# TM_Programmer0_1.net
KiCad netlist of a schematic drawn in EAGLE
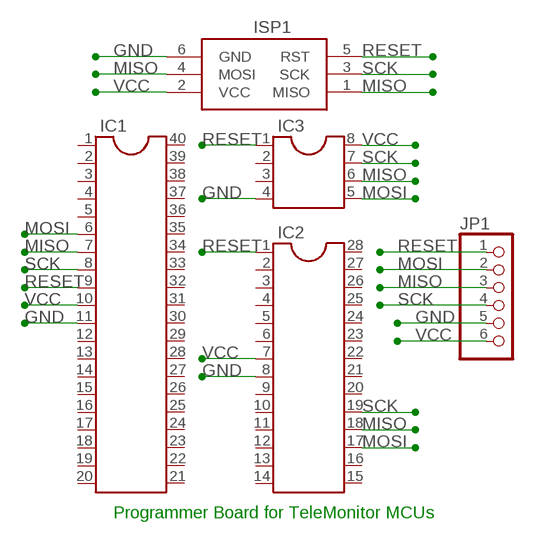
[diagram p0: schematic, sheet 1]

(export (version "E")
  (design (tool "Eeschema 10.0.6"))
  (components
    (comp (ref "IC1")
      (value "DIL40")
      (footprint "eagle-import:DIL40")
      (libsource (lib "eagle-import") (part "DIL40"))
    )
    (comp (ref "IC2")
      (value "DIL28-3")
      (footprint "eagle-import:DIL28-3")
      (libsource (lib "eagle-import") (part "DIL28-3"))
    )
    (comp (ref "IC3")
      (value "DIL8S")
      (footprint "eagle-import:SOCKET-08")
      (libsource (lib "eagle-import") (part "DIL8S"))
    )
    (comp (ref "ISP1")
      (value "AVRISP-6")
      (footprint "eagle-import:AVRISP")
      (libsource (lib "eagle-import") (part "AVRISP-6"))
    )
    (comp (ref "JP1")
      (value "PINHD-1X6")
      (footprint "eagle-import:1X06")
      (libsource (lib "eagle-import") (part "PINHD-1X6"))
    )
  )
  (nets
    (net (code "1") (name "/GND") (class "Default")
      (node (ref "IC1") (pin "11") (pinfunction "11_11") (pintype "passive"))
      (node (ref "IC2") (pin "8") (pinfunction "8_8") (pintype "passive"))
      (node (ref "IC3") (pin "4") (pinfunction "4_4") (pintype "passive"))
      (node (ref "ISP1") (pin "6") (pinfunction "GND_6") (pintype "power_in"))
      (node (ref "JP1") (pin "5") (pinfunction "5_5") (pintype "passive"))
    )
    (net (code "2") (name "/MISO") (class "Default")
      (node (ref "IC1") (pin "7") (pinfunction "7_7") (pintype "passive"))
      (node (ref "IC2") (pin "18") (pinfunction "18_18") (pintype "passive"))
      (node (ref "IC3") (pin "6") (pinfunction "6_6") (pintype "passive"))
      (node (ref "ISP1") (pin "1") (pinfunction "MISO_1") (pintype "input"))
      (node (ref "ISP1") (pin "4") (pinfunction "MOSI_4") (pintype "output"))
      (node (ref "JP1") (pin "3") (pinfunction "3_3") (pintype "passive"))
    )
    (net (code "3") (name "/MOSI") (class "Default")
      (node (ref "IC1") (pin "6") (pinfunction "6_6") (pintype "passive"))
      (node (ref "IC2") (pin "17") (pinfunction "17_17") (pintype "passive"))
      (node (ref "IC3") (pin "5") (pinfunction "5_5") (pintype "passive"))
      (node (ref "JP1") (pin "2") (pinfunction "2_2") (pintype "passive"))
    )
    (net (code "4") (name "/RESET") (class "Default")
      (node (ref "IC1") (pin "9") (pinfunction "9_9") (pintype "passive"))
      (node (ref "IC2") (pin "1") (pinfunction "1_1") (pintype "passive"))
      (node (ref "IC3") (pin "1") (pinfunction "1_1") (pintype "passive"))
      (node (ref "ISP1") (pin "5") (pinfunction "RST_5") (pintype "output"))
      (node (ref "JP1") (pin "1") (pinfunction "1_1") (pintype "passive"))
    )
    (net (code "5") (name "/SCK") (class "Default")
      (node (ref "IC1") (pin "8") (pinfunction "8_8") (pintype "passive"))
      (node (ref "IC2") (pin "19") (pinfunction "19_19") (pintype "passive"))
      (node (ref "IC3") (pin "7") (pinfunction "7_7") (pintype "passive"))
      (node (ref "ISP1") (pin "3") (pinfunction "SCK_3") (pintype "output"))
      (node (ref "JP1") (pin "4") (pinfunction "4_4") (pintype "passive"))
    )
    (net (code "6") (name "/VCC") (class "Default")
      (node (ref "IC1") (pin "10") (pinfunction "10_10") (pintype "passive"))
      (node (ref "IC2") (pin "7") (pinfunction "7_7") (pintype "passive"))
      (node (ref "IC3") (pin "8") (pinfunction "8_8") (pintype "passive"))
      (node (ref "ISP1") (pin "2") (pinfunction "VCC_2") (pintype "power_in"))
      (node (ref "JP1") (pin "6") (pinfunction "6_6") (pintype "passive"))
    )
    (net (code "7") (name "unconnected-(IC1-Pad1)") (class "Default")
      (node (ref "IC1") (pin "1") (pinfunction "1_1") (pintype "passive"))
    )
    (net (code "8") (name "unconnected-(IC1-Pad2)") (class "Default")
      (node (ref "IC1") (pin "2") (pinfunction "2_2") (pintype "passive"))
    )
    (net (code "9") (name "unconnected-(IC1-Pad3)") (class "Default")
      (node (ref "IC1") (pin "3") (pinfunction "3_3") (pintype "passive"))
    )
    (net (code "10") (name "unconnected-(IC1-Pad4)") (class "Default")
      (node (ref "IC1") (pin "4") (pinfunction "4_4") (pintype "passive"))
    )
    (net (code "11") (name "unconnected-(IC1-Pad5)") (class "Default")
      (node (ref "IC1") (pin "5") (pinfunction "5_5") (pintype "passive"))
    )
    (net (code "12") (name "unconnected-(IC1-Pad12)") (class "Default")
      (node (ref "IC1") (pin "12") (pinfunction "12_12") (pintype "passive"))
    )
    (net (code "13") (name "unconnected-(IC1-Pad13)") (class "Default")
      (node (ref "IC1") (pin "13") (pinfunction "13_13") (pintype "passive"))
    )
    (net (code "14") (name "unconnected-(IC1-Pad14)") (class "Default")
      (node (ref "IC1") (pin "14") (pinfunction "14_14") (pintype "passive"))
    )
    (net (code "15") (name "unconnected-(IC1-Pad15)") (class "Default")
      (node (ref "IC1") (pin "15") (pinfunction "15_15") (pintype "passive"))
    )
    (net (code "16") (name "unconnected-(IC1-Pad16)") (class "Default")
      (node (ref "IC1") (pin "16") (pinfunction "16_16") (pintype "passive"))
    )
    (net (code "17") (name "unconnected-(IC1-Pad17)") (class "Default")
      (node (ref "IC1") (pin "17") (pinfunction "17_17") (pintype "passive"))
    )
    (net (code "18") (name "unconnected-(IC1-Pad18)") (class "Default")
      (node (ref "IC1") (pin "18") (pinfunction "18_18") (pintype "passive"))
    )
    (net (code "19") (name "unconnected-(IC1-Pad19)") (class "Default")
      (node (ref "IC1") (pin "19") (pinfunction "19_19") (pintype "passive"))
    )
    (net (code "20") (name "unconnected-(IC1-Pad20)") (class "Default")
      (node (ref "IC1") (pin "20") (pinfunction "20_20") (pintype "passive"))
    )
    (net (code "21") (name "unconnected-(IC1-Pad21)") (class "Default")
      (node (ref "IC1") (pin "21") (pinfunction "21_21") (pintype "passive"))
    )
    (net (code "22") (name "unconnected-(IC1-Pad22)") (class "Default")
      (node (ref "IC1") (pin "22") (pinfunction "22_22") (pintype "passive"))
    )
    (net (code "23") (name "unconnected-(IC1-Pad23)") (class "Default")
      (node (ref "IC1") (pin "23") (pinfunction "23_23") (pintype "passive"))
    )
    (net (code "24") (name "unconnected-(IC1-Pad24)") (class "Default")
      (node (ref "IC1") (pin "24") (pinfunction "24_24") (pintype "passive"))
    )
    (net (code "25") (name "unconnected-(IC1-Pad25)") (class "Default")
      (node (ref "IC1") (pin "25") (pinfunction "25_25") (pintype "passive"))
    )
    (net (code "26") (name "unconnected-(IC1-Pad26)") (class "Default")
      (node (ref "IC1") (pin "26") (pinfunction "26_26") (pintype "passive"))
    )
    (net (code "27") (name "unconnected-(IC1-Pad27)") (class "Default")
      (node (ref "IC1") (pin "27") (pinfunction "27_27") (pintype "passive"))
    )
    (net (code "28") (name "unconnected-(IC1-Pad28)") (class "Default")
      (node (ref "IC1") (pin "28") (pinfunction "28_28") (pintype "passive"))
    )
    (net (code "29") (name "unconnected-(IC1-Pad29)") (class "Default")
      (node (ref "IC1") (pin "29") (pinfunction "29_29") (pintype "passive"))
    )
    (net (code "30") (name "unconnected-(IC1-Pad30)") (class "Default")
      (node (ref "IC1") (pin "30") (pinfunction "30_30") (pintype "passive"))
    )
    (net (code "31") (name "unconnected-(IC1-Pad31)") (class "Default")
      (node (ref "IC1") (pin "31") (pinfunction "31_31") (pintype "passive"))
    )
    (net (code "32") (name "unconnected-(IC1-Pad32)") (class "Default")
      (node (ref "IC1") (pin "32") (pinfunction "32_32") (pintype "passive"))
    )
    (net (code "33") (name "unconnected-(IC1-Pad33)") (class "Default")
      (node (ref "IC1") (pin "33") (pinfunction "33_33") (pintype "passive"))
    )
    (net (code "34") (name "unconnected-(IC1-Pad34)") (class "Default")
      (node (ref "IC1") (pin "34") (pinfunction "34_34") (pintype "passive"))
    )
    (net (code "35") (name "unconnected-(IC1-Pad35)") (class "Default")
      (node (ref "IC1") (pin "35") (pinfunction "35_35") (pintype "passive"))
    )
    (net (code "36") (name "unconnected-(IC1-Pad36)") (class "Default")
      (node (ref "IC1") (pin "36") (pinfunction "36_36") (pintype "passive"))
    )
    (net (code "37") (name "unconnected-(IC1-Pad37)") (class "Default")
      (node (ref "IC1") (pin "37") (pinfunction "37_37") (pintype "passive"))
    )
    (net (code "38") (name "unconnected-(IC1-Pad38)") (class "Default")
      (node (ref "IC1") (pin "38") (pinfunction "38_38") (pintype "passive"))
    )
    (net (code "39") (name "unconnected-(IC1-Pad39)") (class "Default")
      (node (ref "IC1") (pin "39") (pinfunction "39_39") (pintype "passive"))
    )
    (net (code "40") (name "unconnected-(IC1-Pad40)") (class "Default")
      (node (ref "IC1") (pin "40") (pinfunction "40_40") (pintype "passive"))
    )
    (net (code "41") (name "unconnected-(IC2-Pad2)") (class "Default")
      (node (ref "IC2") (pin "2") (pinfunction "2_2") (pintype "passive"))
    )
    (net (code "42") (name "unconnected-(IC2-Pad3)") (class "Default")
      (node (ref "IC2") (pin "3") (pinfunction "3_3") (pintype "passive"))
    )
    (net (code "43") (name "unconnected-(IC2-Pad4)") (class "Default")
      (node (ref "IC2") (pin "4") (pinfunction "4_4") (pintype "passive"))
    )
    (net (code "44") (name "unconnected-(IC2-Pad5)") (class "Default")
      (node (ref "IC2") (pin "5") (pinfunction "5_5") (pintype "passive"))
    )
    (net (code "45") (name "unconnected-(IC2-Pad6)") (class "Default")
      (node (ref "IC2") (pin "6") (pinfunction "6_6") (pintype "passive"))
    )
    (net (code "46") (name "unconnected-(IC2-Pad9)") (class "Default")
      (node (ref "IC2") (pin "9") (pinfunction "9_9") (pintype "passive"))
    )
    (net (code "47") (name "unconnected-(IC2-Pad10)") (class "Default")
      (node (ref "IC2") (pin "10") (pinfunction "10_10") (pintype "passive"))
    )
    (net (code "48") (name "unconnected-(IC2-Pad11)") (class "Default")
      (node (ref "IC2") (pin "11") (pinfunction "11_11") (pintype "passive"))
    )
    (net (code "49") (name "unconnected-(IC2-Pad12)") (class "Default")
      (node (ref "IC2") (pin "12") (pinfunction "12_12") (pintype "passive"))
    )
    (net (code "50") (name "unconnected-(IC2-Pad13)") (class "Default")
      (node (ref "IC2") (pin "13") (pinfunction "13_13") (pintype "passive"))
    )
    (net (code "51") (name "unconnected-(IC2-Pad14)") (class "Default")
      (node (ref "IC2") (pin "14") (pinfunction "14_14") (pintype "passive"))
    )
    (net (code "52") (name "unconnected-(IC2-Pad15)") (class "Default")
      (node (ref "IC2") (pin "15") (pinfunction "15_15") (pintype "passive"))
    )
    (net (code "53") (name "unconnected-(IC2-Pad16)") (class "Default")
      (node (ref "IC2") (pin "16") (pinfunction "16_16") (pintype "passive"))
    )
    (net (code "54") (name "unconnected-(IC2-Pad20)") (class "Default")
      (node (ref "IC2") (pin "20") (pinfunction "20_20") (pintype "passive"))
    )
    (net (code "55") (name "unconnected-(IC2-Pad21)") (class "Default")
      (node (ref "IC2") (pin "21") (pinfunction "21_21") (pintype "passive"))
    )
    (net (code "56") (name "unconnected-(IC2-Pad22)") (class "Default")
      (node (ref "IC2") (pin "22") (pinfunction "22_22") (pintype "passive"))
    )
    (net (code "57") (name "unconnected-(IC2-Pad23)") (class "Default")
      (node (ref "IC2") (pin "23") (pinfunction "23_23") (pintype "passive"))
    )
    (net (code "58") (name "unconnected-(IC2-Pad24)") (class "Default")
      (node (ref "IC2") (pin "24") (pinfunction "24_24") (pintype "passive"))
    )
    (net (code "59") (name "unconnected-(IC2-Pad25)") (class "Default")
      (node (ref "IC2") (pin "25") (pinfunction "25_25") (pintype "passive"))
    )
    (net (code "60") (name "unconnected-(IC2-Pad26)") (class "Default")
      (node (ref "IC2") (pin "26") (pinfunction "26_26") (pintype "passive"))
    )
    (net (code "61") (name "unconnected-(IC2-Pad27)") (class "Default")
      (node (ref "IC2") (pin "27") (pinfunction "27_27") (pintype "passive"))
    )
    (net (code "62") (name "unconnected-(IC2-Pad28)") (class "Default")
      (node (ref "IC2") (pin "28") (pinfunction "28_28") (pintype "passive"))
    )
    (net (code "63") (name "unconnected-(IC3-Pad2)") (class "Default")
      (node (ref "IC3") (pin "2") (pinfunction "2_2") (pintype "passive"))
    )
    (net (code "64") (name "unconnected-(IC3-Pad3)") (class "Default")
      (node (ref "IC3") (pin "3") (pinfunction "3_3") (pintype "passive"))
    )
  )
)
